# VREG_AOZ1284PI_5V_4A.net
KiCad netlist of a schematic drawn in Altium Designer
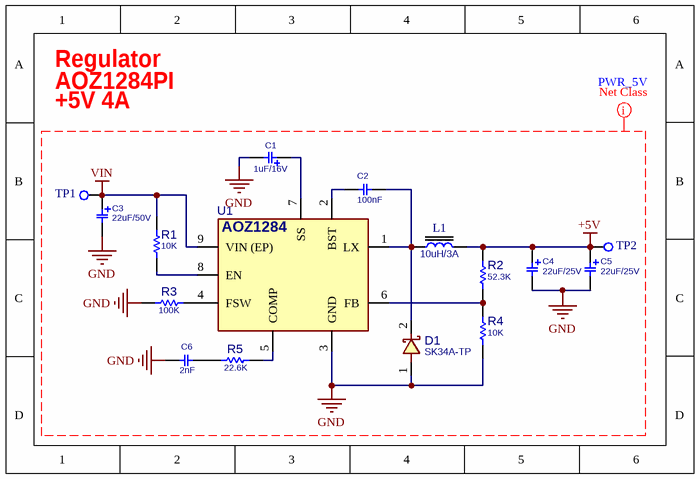
[diagram p0: VREG AOZ1284PI +5V 4A.SchDoc]

(export (version "E")
  (design (tool "Eeschema 10.0.6"))
  (components
    (comp (ref "C1")
      (value "1uF/16V")
      (footprint "C_TN_A")
      (description "CAP, SMD, TAN")
      (libsource (lib "Passive") (part "CAP_SMD_TAN"))
    )
    (comp (ref "C2")
      (value "100nF")
      (footprint "C0603S")
      (description "CAP, SMD, MLCC")
      (fields (field (name "MANF_P#") "MANF_PART#") (field (name "MANF") "Murata"))
      (libsource (lib "Passive") (part "CAP_SMD_MLCC"))
    )
    (comp (ref "C3")
      (value "22uF/50V")
      (footprint "C_TN_A")
      (description "CAP, SMD, TAN")
      (libsource (lib "Passive") (part "CAP_SMD_TAN"))
    )
    (comp (ref "C4")
      (value "22uF/25V")
      (footprint "C_TN_A")
      (description "CAP, SMD, TAN")
      (libsource (lib "Passive") (part "CAP_SMD_TAN"))
    )
    (comp (ref "C5")
      (value "22uF/25V")
      (footprint "C_TN_A")
      (description "CAP, SMD, TAN")
      (libsource (lib "Passive") (part "CAP_SMD_TAN"))
    )
    (comp (ref "C6")
      (value "2nF")
      (footprint "C0603S")
      (description "CAP, SMD, MLCC")
      (fields (field (name "MANF_P#") "MANF_PART#") (field (name "MANF") "Murata"))
      (libsource (lib "Passive") (part "CAP_SMD_MLCC"))
    )
    (comp (ref "D1")
      (value "SK34A-TP")
      (footprint "D_SMA")
      (description "DIODE, SCHOTTKY, 40V, 3A")
      (fields (field (name "MANF") "Vishay") (field (name "MANF_P#") "SS14-E3"))
      (libsource (lib "PW Components 97_492") (part "DIODE_SMD_SCHOTTKY_SK34A-TP"))
    )
    (comp (ref "L1")
      (value "10uH/3A")
      (footprint "L_8X8")
      (description "IND, PWR, SMD")
      (libsource (lib "Passive") (part "INDPWR_SMD"))
    )
    (comp (ref "R1")
      (value "10K")
      (footprint "R0603S")
      (description "RES, SMD")
      (fields (field (name "MANF_P#") "RK73H1ETTP4701F") (field (name "MANF") "KOA SPEER"))
      (libsource (lib "Passive") (part "RES_SMD"))
    )
    (comp (ref "R2")
      (value "52.3K")
      (footprint "R0603S")
      (description "RES, SMD")
      (fields (field (name "MANF_P#") "RK73H1ETTP4701F") (field (name "MANF") "KOA SPEER"))
      (libsource (lib "Passive") (part "RES_SMD"))
    )
    (comp (ref "R3")
      (value "100K")
      (footprint "R0603S")
      (description "RES, SMD")
      (fields (field (name "MANF_P#") "RK73H1ETTP4701F") (field (name "MANF") "KOA SPEER"))
      (libsource (lib "Passive") (part "RES_SMD"))
    )
    (comp (ref "R4")
      (value "10K")
      (footprint "R0603S")
      (description "RES, SMD")
      (fields (field (name "MANF_P#") "RK73H1ETTP4701F") (field (name "MANF") "KOA SPEER"))
      (libsource (lib "Passive") (part "RES_SMD"))
    )
    (comp (ref "R5")
      (value "22.6K")
      (footprint "R0603S")
      (description "RES, SMD")
      (fields (field (name "MANF_P#") "RK73H1ETTP4701F") (field (name "MANF") "KOA SPEER"))
      (libsource (lib "Passive") (part "RES_SMD"))
    )
    (comp (ref "TP1")
      (value "Test Point")
      (footprint "TPSMD_C1")
      (libsource (lib "PW Components") (part "Test Point"))
    )
    (comp (ref "TP2")
      (value "Test Point")
      (footprint "TPSMD_C1")
      (libsource (lib "PW Components") (part "Test Point"))
    )
    (comp (ref "U1")
      (value "AOZ1021AI")
      (footprint "SO_8T")
      (description "REG, Switching, Buck, 4A, ADJ, 500KHz, 3~36VIN, SO-8")
      (fields (field (name "MANF") "AOSMD"))
      (libsource (lib "PW Components 97_492") (part "VREG_AOZ1284PI_SO8"))
    )
  )
  (nets
    (net (code "1") (name "+5V") (class "Default")
      (node (ref "C4") (pin "1") (pinfunction "1_1") (pintype "passive"))
      (node (ref "C5") (pin "1") (pinfunction "1_1") (pintype "passive"))
      (node (ref "L1") (pin "2") (pinfunction "2_2") (pintype "passive"))
      (node (ref "R2") (pin "1") (pinfunction "1_1") (pintype "passive"))
      (node (ref "TP2") (pin "1") (pinfunction "TP_1") (pintype "passive"))
    )
    (net (code "2") (name "GND") (class "Default")
      (node (ref "C1") (pin "2") (pinfunction "2_2") (pintype "passive"))
      (node (ref "C3") (pin "2") (pinfunction "2_2") (pintype "passive"))
      (node (ref "C4") (pin "2") (pinfunction "2_2") (pintype "passive"))
      (node (ref "C5") (pin "2") (pinfunction "2_2") (pintype "passive"))
      (node (ref "C6") (pin "2") (pinfunction "2_2") (pintype "passive"))
      (node (ref "D1") (pin "1") (pinfunction "1_1") (pintype "passive"))
      (node (ref "R3") (pin "1") (pinfunction "1_1") (pintype "passive"))
      (node (ref "R4") (pin "2") (pinfunction "2_2") (pintype "passive"))
      (node (ref "U1") (pin "3") (pinfunction "GND_3") (pintype "power_in"))
    )
    (net (code "3") (name "Net-(C6-Pad1)") (class "Default")
      (node (ref "C6") (pin "1") (pinfunction "1_1") (pintype "passive"))
      (node (ref "R5") (pin "1") (pinfunction "1_1") (pintype "passive"))
    )
    (net (code "4") (name "Net-(U1-BST)") (class "Default")
      (node (ref "C2") (pin "2") (pinfunction "2_2") (pintype "passive"))
      (node (ref "U1") (pin "2") (pinfunction "BST_2") (pintype "passive"))
    )
    (net (code "5") (name "Net-(U1-COMP)") (class "Default")
      (node (ref "R5") (pin "2") (pinfunction "2_2") (pintype "passive"))
      (node (ref "U1") (pin "5") (pinfunction "COMP_5") (pintype "power_in"))
    )
    (net (code "6") (name "Net-(U1-EN)") (class "Default")
      (node (ref "R1") (pin "2") (pinfunction "2_2") (pintype "passive"))
      (node (ref "U1") (pin "8") (pinfunction "EN_8") (pintype "passive"))
    )
    (net (code "7") (name "Net-(U1-FB)") (class "Default")
      (node (ref "R2") (pin "2") (pinfunction "2_2") (pintype "passive"))
      (node (ref "R4") (pin "1") (pinfunction "1_1") (pintype "passive"))
      (node (ref "U1") (pin "6") (pinfunction "FB_6") (pintype "passive"))
    )
    (net (code "8") (name "Net-(U1-FSW)") (class "Default")
      (node (ref "R3") (pin "2") (pinfunction "2_2") (pintype "passive"))
      (node (ref "U1") (pin "4") (pinfunction "FSW_4") (pintype "passive"))
    )
    (net (code "9") (name "Net-(U1-LX)") (class "Default")
      (node (ref "C2") (pin "1") (pinfunction "1_1") (pintype "passive"))
      (node (ref "D1") (pin "2") (pinfunction "2_2") (pintype "passive"))
      (node (ref "L1") (pin "1") (pinfunction "1_1") (pintype "passive"))
      (node (ref "U1") (pin "1") (pinfunction "LX_1") (pintype "passive"))
    )
    (net (code "10") (name "Net-(U1-SS)") (class "Default")
      (node (ref "C1") (pin "1") (pinfunction "1_1") (pintype "passive"))
      (node (ref "U1") (pin "7") (pinfunction "SS_7") (pintype "passive"))
    )
    (net (code "11") (name "VIN") (class "Default")
      (node (ref "C3") (pin "1") (pinfunction "1_1") (pintype "passive"))
      (node (ref "R1") (pin "1") (pinfunction "1_1") (pintype "passive"))
      (node (ref "TP1") (pin "1") (pinfunction "TP_1") (pintype "passive"))
      (node (ref "U1") (pin "9") (pinfunction "VIN_(EP)_9") (pintype "power_in"))
    )
  )
)
